# 05_LMS7002M_RF.net
KiCad netlist of a schematic drawn in Altium Designer
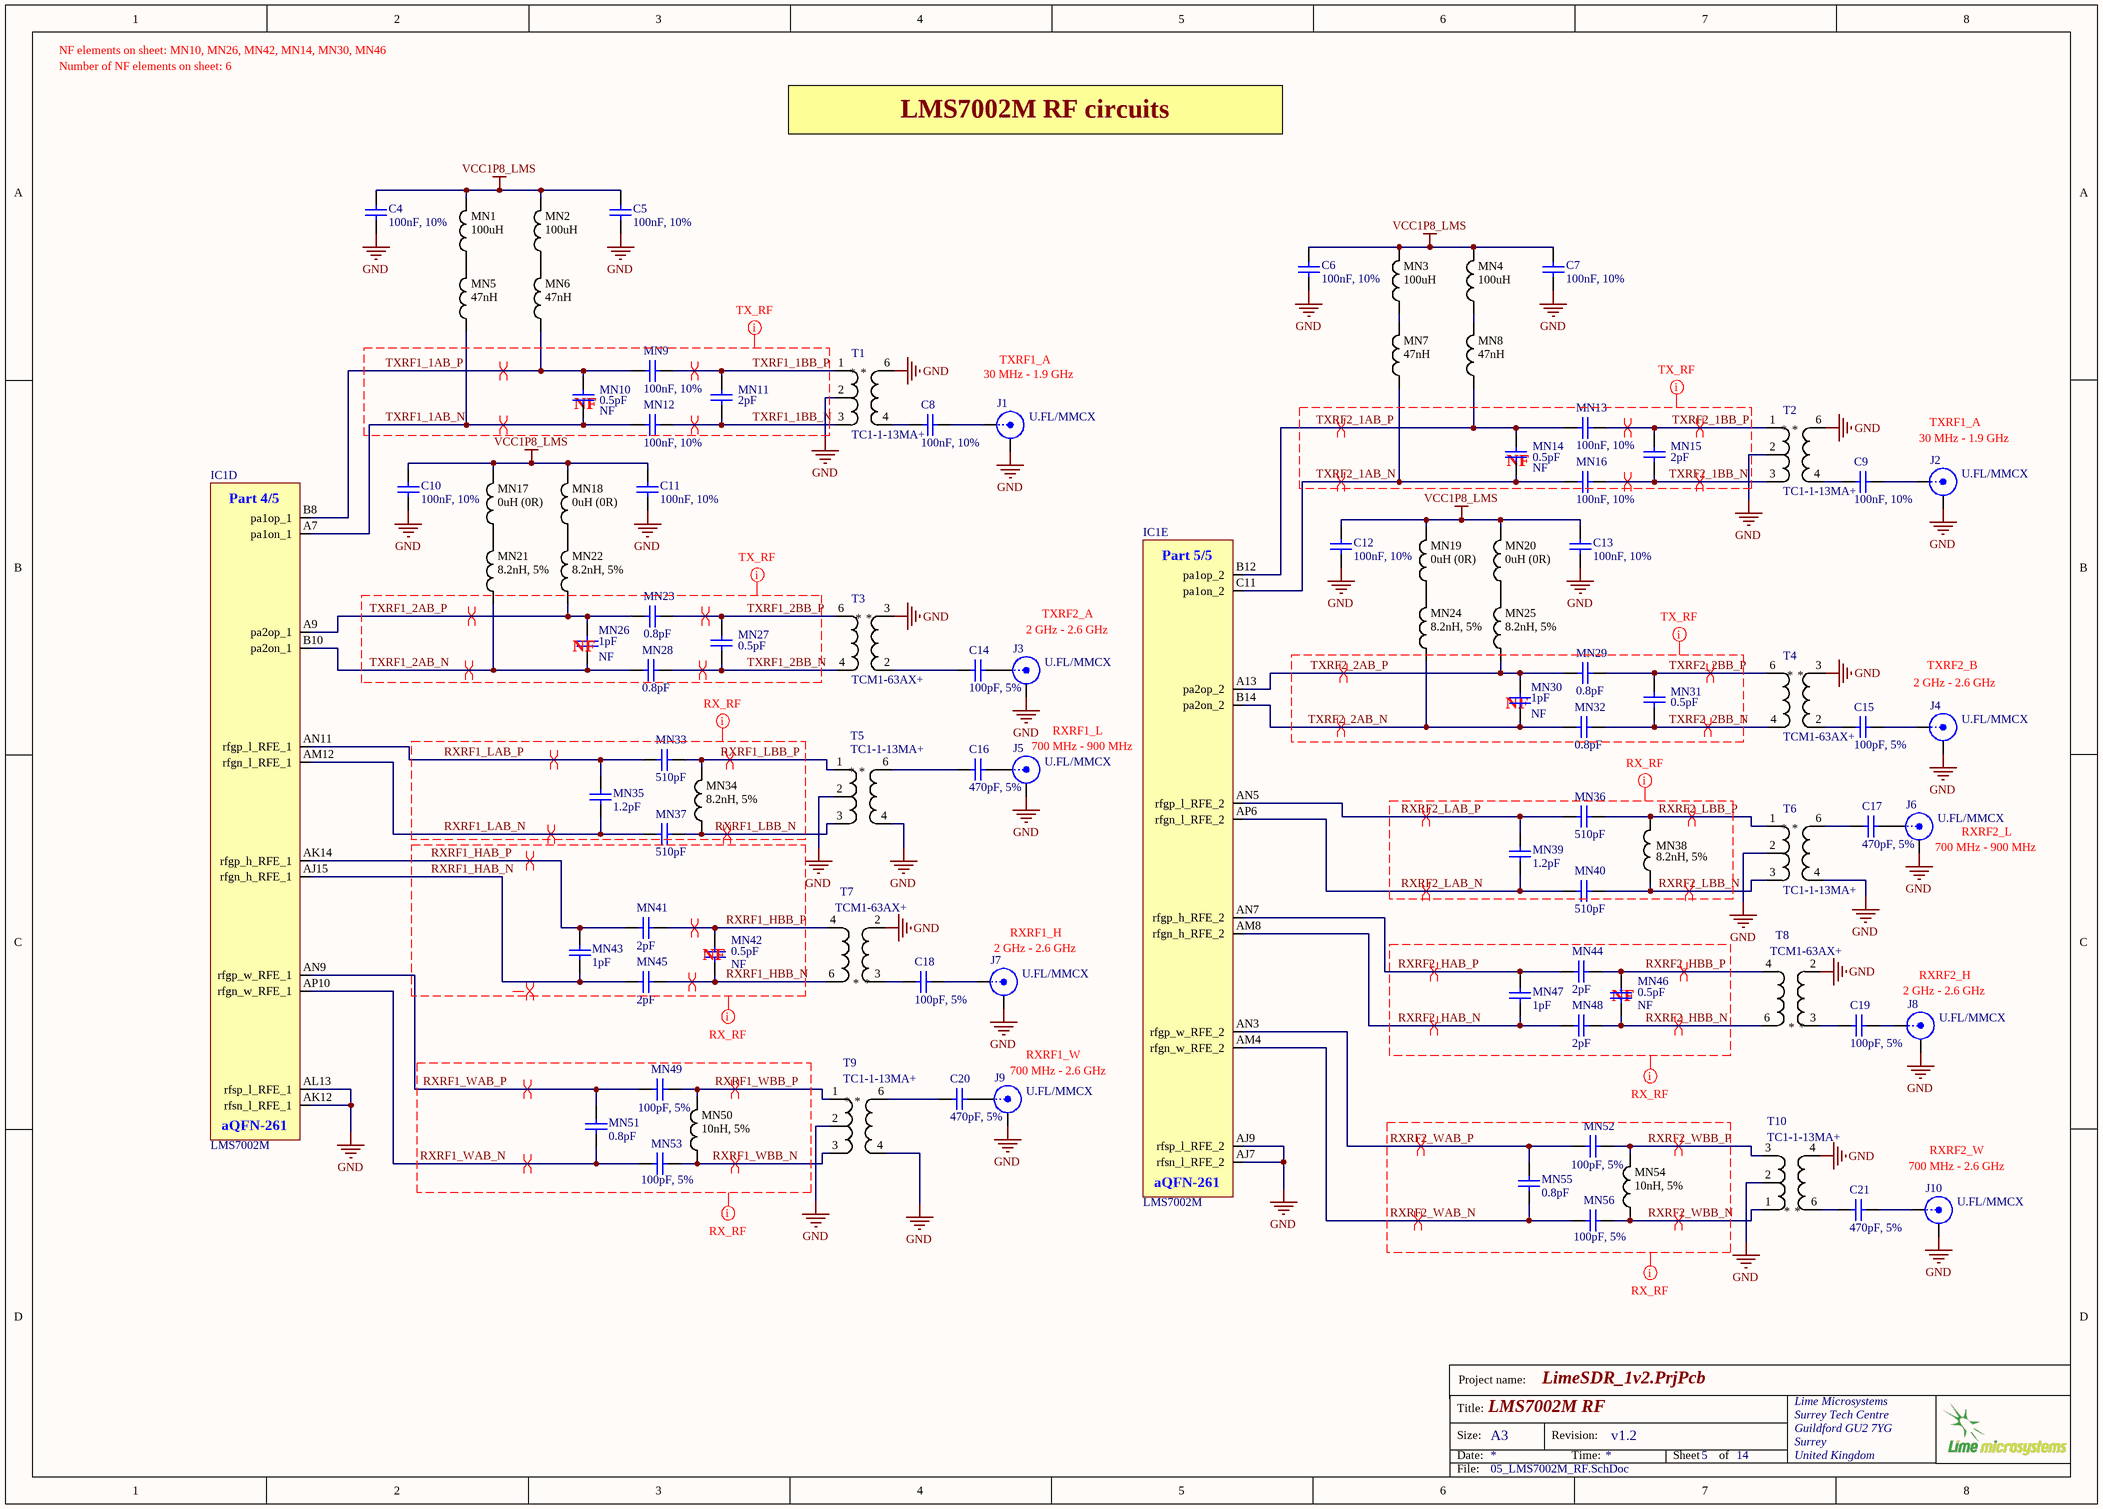
[diagram p0: 05_LMS7002M_RF.SchDoc]

(export (version "E")
  (design (tool "Eeschema 10.0.6"))
  (components
    (comp (ref "C4")
      (value "100nF, 10%")
      (footprint "CAP0402")
      (fields
        (field (name "MANUFACTURER") "Murata Electronics")
        (field (name "TOLERANCE") "10 %")
        (field (name "MANUFACTURER PART NUMBER") "GRM155R71C104KA88D")
      )
      (libsource (lib "LimeMicroAltiumLib_schLib") (part "Cap_0402"))
    )
    (comp (ref "C5")
      (value "100nF, 10%")
      (footprint "CAP0402")
      (fields
        (field (name "MANUFACTURER") "Murata Electronics")
        (field (name "TOLERANCE") "10 %")
        (field (name "MANUFACTURER PART NUMBER") "GRM155R71C104KA88D")
      )
      (libsource (lib "LimeMicroAltiumLib_schLib") (part "Cap_0402"))
    )
    (comp (ref "C6")
      (value "100nF, 10%")
      (footprint "CAP0402")
      (fields
        (field (name "MANUFACTURER") "Murata Electronics")
        (field (name "TOLERANCE") "10 %")
        (field (name "MANUFACTURER PART NUMBER") "GRM155R71C104KA88D")
      )
      (libsource (lib "LimeMicroAltiumLib_schLib") (part "Cap_0402"))
    )
    (comp (ref "C7")
      (value "100nF, 10%")
      (footprint "CAP0402")
      (fields
        (field (name "MANUFACTURER") "Murata Electronics")
        (field (name "TOLERANCE") "10 %")
        (field (name "MANUFACTURER PART NUMBER") "GRM155R71C104KA88D")
      )
      (libsource (lib "LimeMicroAltiumLib_schLib") (part "Cap_0402"))
    )
    (comp (ref "C8")
      (value "100nF, 10%")
      (footprint "CAP0402")
      (fields
        (field (name "MANUFACTURER") "Murata Electronics")
        (field (name "TOLERANCE") "10 %")
        (field (name "MANUFACTURER PART NUMBER") "GRM155R71C104KA88D")
      )
      (libsource (lib "LimeMicroAltiumLib_schLib") (part "Cap_0402"))
    )
    (comp (ref "C9")
      (value "100nF, 10%")
      (footprint "CAP0402")
      (fields
        (field (name "MANUFACTURER") "Murata Electronics")
        (field (name "TOLERANCE") "10 %")
        (field (name "MANUFACTURER PART NUMBER") "GRM155R71C104KA88D")
      )
      (libsource (lib "LimeMicroAltiumLib_schLib") (part "Cap_0402"))
    )
    (comp (ref "C10")
      (value "100nF, 10%")
      (footprint "CAP0402")
      (fields
        (field (name "MANUFACTURER") "Murata Electronics")
        (field (name "TOLERANCE") "10 %")
        (field (name "MANUFACTURER PART NUMBER") "GRM155R71C104KA88D")
      )
      (libsource (lib "LimeMicroAltiumLib_schLib") (part "Cap_0402"))
    )
    (comp (ref "C11")
      (value "100nF, 10%")
      (footprint "CAP0402")
      (fields
        (field (name "MANUFACTURER") "Murata Electronics")
        (field (name "TOLERANCE") "10 %")
        (field (name "MANUFACTURER PART NUMBER") "GRM155R71C104KA88D")
      )
      (libsource (lib "LimeMicroAltiumLib_schLib") (part "Cap_0402"))
    )
    (comp (ref "C12")
      (value "100nF, 10%")
      (footprint "CAP0402")
      (fields
        (field (name "MANUFACTURER") "Murata Electronics")
        (field (name "TOLERANCE") "10 %")
        (field (name "MANUFACTURER PART NUMBER") "GRM155R71C104KA88D")
      )
      (libsource (lib "LimeMicroAltiumLib_schLib") (part "Cap_0402"))
    )
    (comp (ref "C13")
      (value "100nF, 10%")
      (footprint "CAP0402")
      (fields
        (field (name "MANUFACTURER") "Murata Electronics")
        (field (name "TOLERANCE") "10 %")
        (field (name "MANUFACTURER PART NUMBER") "GRM155R71C104KA88D")
      )
      (libsource (lib "LimeMicroAltiumLib_schLib") (part "Cap_0402"))
    )
    (comp (ref "C14")
      (value "100pF, 5%")
      (footprint "CAP0402")
      (fields (field (name "TOLERANCE") "±5%") (field (name "MANUFACTURER") "Yageo"))
      (libsource (lib "LimeMicroAltiumLib_schLib") (part "Cap_0402"))
    )
    (comp (ref "C15")
      (value "100pF, 5%")
      (footprint "CAP0402")
      (fields (field (name "TOLERANCE") "±5%") (field (name "MANUFACTURER") "Yageo"))
      (libsource (lib "LimeMicroAltiumLib_schLib") (part "Cap_0402"))
    )
    (comp (ref "C16")
      (value "470pF, 5%")
      (footprint "CAP0402")
      (fields
        (field (name "MANUFACTURER PART NUMBER") "C1005C0G1H471J050BA")
        (field (name "TOLERANCE") "±5%")
        (field (name "MANUFACTURER") "TDK Corporation")
      )
      (libsource (lib "LimeMicroAltiumLib_schLib") (part "Cap_0402"))
    )
    (comp (ref "C17")
      (value "470pF, 5%")
      (footprint "CAP0402")
      (fields
        (field (name "MANUFACTURER PART NUMBER") "C1005C0G1H471J050BA")
        (field (name "TOLERANCE") "±5%")
        (field (name "MANUFACTURER") "TDK Corporation")
      )
      (libsource (lib "LimeMicroAltiumLib_schLib") (part "Cap_0402"))
    )
    (comp (ref "C18")
      (value "100pF, 5%")
      (footprint "CAP0402")
      (fields (field (name "TOLERANCE") "±5%") (field (name "MANUFACTURER") "Yageo"))
      (libsource (lib "LimeMicroAltiumLib_schLib") (part "Cap_0402"))
    )
    (comp (ref "C19")
      (value "100pF, 5%")
      (footprint "CAP0402")
      (fields (field (name "TOLERANCE") "±5%") (field (name "MANUFACTURER") "Yageo"))
      (libsource (lib "LimeMicroAltiumLib_schLib") (part "Cap_0402"))
    )
    (comp (ref "C20")
      (value "470pF, 5%")
      (footprint "CAP0402")
      (fields
        (field (name "MANUFACTURER PART NUMBER") "C1005C0G1H471J050BA")
        (field (name "TOLERANCE") "±5%")
        (field (name "MANUFACTURER") "TDK Corporation")
      )
      (libsource (lib "LimeMicroAltiumLib_schLib") (part "Cap_0402"))
    )
    (comp (ref "C21")
      (value "470pF, 5%")
      (footprint "CAP0402")
      (fields
        (field (name "MANUFACTURER PART NUMBER") "C1005C0G1H471J050BA")
        (field (name "TOLERANCE") "±5%")
        (field (name "MANUFACTURER") "TDK Corporation")
      )
      (libsource (lib "LimeMicroAltiumLib_schLib") (part "Cap_0402"))
    )
    (comp (ref "IC1")
      (value "LMS7002M")
      (footprint "LMS7002M")
      (fields (field (name "MANUFACTURER") "Lime Microsystems"))
      (libsource (lib "LimeMicroAltiumLib_schLib") (part "LMS7002M"))
    )
    (comp (ref "J1")
      (value "U.FL/MMCX")
      (footprint "MMCX_UFL_conn_u")
      (description "CONN UMC RCPT STR 50 OHM SMD")
      (fields (field (name "MANUFACTURER") "Molex, LLC"))
      (libsource (lib "LimeMicroAltiumLib_schLib") (part "RF_IF_connector"))
    )
    (comp (ref "J2")
      (value "U.FL/MMCX")
      (footprint "MMCX_UFL_conn_u")
      (description "CONN UMC RCPT STR 50 OHM SMD")
      (fields (field (name "MANUFACTURER") "Molex, LLC"))
      (libsource (lib "LimeMicroAltiumLib_schLib") (part "RF_IF_connector"))
    )
    (comp (ref "J3")
      (value "U.FL/MMCX")
      (footprint "MMCX_UFL_conn_u")
      (description "CONN UMC RCPT STR 50 OHM SMD")
      (fields (field (name "MANUFACTURER") "Molex, LLC"))
      (libsource (lib "LimeMicroAltiumLib_schLib") (part "RF_IF_connector"))
    )
    (comp (ref "J4")
      (value "U.FL/MMCX")
      (footprint "MMCX_UFL_conn_u")
      (description "CONN UMC RCPT STR 50 OHM SMD")
      (fields (field (name "MANUFACTURER") "Molex, LLC"))
      (libsource (lib "LimeMicroAltiumLib_schLib") (part "RF_IF_connector"))
    )
    (comp (ref "J5")
      (value "U.FL/MMCX")
      (footprint "MMCX_UFL_conn_u")
      (description "CONN UMC RCPT STR 50 OHM SMD")
      (fields (field (name "MANUFACTURER") "Molex, LLC"))
      (libsource (lib "LimeMicroAltiumLib_schLib") (part "RF_IF_connector"))
    )
    (comp (ref "J6")
      (value "U.FL/MMCX")
      (footprint "MMCX_UFL_conn_u")
      (description "CONN UMC RCPT STR 50 OHM SMD")
      (fields (field (name "MANUFACTURER") "Molex, LLC"))
      (libsource (lib "LimeMicroAltiumLib_schLib") (part "RF_IF_connector"))
    )
    (comp (ref "J7")
      (value "U.FL/MMCX")
      (footprint "MMCX_UFL_conn_u")
      (description "CONN UMC RCPT STR 50 OHM SMD")
      (fields (field (name "MANUFACTURER") "Molex, LLC"))
      (libsource (lib "LimeMicroAltiumLib_schLib") (part "RF_IF_connector"))
    )
    (comp (ref "J8")
      (value "U.FL/MMCX")
      (footprint "MMCX_UFL_conn_u")
      (description "CONN UMC RCPT STR 50 OHM SMD")
      (fields (field (name "MANUFACTURER") "Molex, LLC"))
      (libsource (lib "LimeMicroAltiumLib_schLib") (part "RF_IF_connector"))
    )
    (comp (ref "J9")
      (value "U.FL/MMCX")
      (footprint "MMCX_UFL_conn_u")
      (description "CONN UMC RCPT STR 50 OHM SMD")
      (fields (field (name "MANUFACTURER") "Molex, LLC"))
      (libsource (lib "LimeMicroAltiumLib_schLib") (part "RF_IF_connector"))
    )
    (comp (ref "J10")
      (value "U.FL/MMCX")
      (footprint "MMCX_UFL_conn_u")
      (description "CONN UMC RCPT STR 50 OHM SMD")
      (fields (field (name "MANUFACTURER") "Molex, LLC"))
      (libsource (lib "LimeMicroAltiumLib_schLib") (part "RF_IF_connector"))
    )
    (comp (ref "MN1")
      (value "100uH")
      (footprint "RES0805")
      (fields
        (field (name "TOLERANCE") "±10%")
        (field (name "MANUFACTURER") "TDK Corporation")
        (field (name "MANUFACTURER PART NUMBER") "MLF2012C101KT000")
      )
      (libsource (lib "LimeMicroAltiumLib_schLib") (part "Inductor_0603"))
    )
    (comp (ref "MN2")
      (value "100uH")
      (footprint "RES0805")
      (fields
        (field (name "TOLERANCE") "±10%")
        (field (name "MANUFACTURER") "TDK Corporation")
        (field (name "MANUFACTURER PART NUMBER") "MLF2012C101KT000")
      )
      (libsource (lib "LimeMicroAltiumLib_schLib") (part "Inductor_0603"))
    )
    (comp (ref "MN3")
      (value "100uH")
      (footprint "RES0805")
      (fields
        (field (name "TOLERANCE") "±10%")
        (field (name "MANUFACTURER") "TDK Corporation")
        (field (name "MANUFACTURER PART NUMBER") "MLF2012C101KT000")
      )
      (libsource (lib "LimeMicroAltiumLib_schLib") (part "Inductor_0603"))
    )
    (comp (ref "MN4")
      (value "100uH")
      (footprint "RES0805")
      (fields
        (field (name "TOLERANCE") "±10%")
        (field (name "MANUFACTURER") "TDK Corporation")
        (field (name "MANUFACTURER PART NUMBER") "MLF2012C101KT000")
      )
      (libsource (lib "LimeMicroAltiumLib_schLib") (part "Inductor_0603"))
    )
    (comp (ref "MN5")
      (value "47nH")
      (footprint "RES0402")
      (fields
        (field (name "MANUFACTURER") "COILCRAFT")
        (field (name "MANUFACTURER PART NUMBER") "0402HP-47NXJLU")
      )
      (libsource (lib "LimeMicroAltiumLib_schLib") (part "Inductor_0603"))
    )
    (comp (ref "MN6")
      (value "47nH")
      (footprint "RES0402")
      (fields
        (field (name "MANUFACTURER") "COILCRAFT")
        (field (name "MANUFACTURER PART NUMBER") "0402HP-47NXJLU")
      )
      (libsource (lib "LimeMicroAltiumLib_schLib") (part "Inductor_0603"))
    )
    (comp (ref "MN7")
      (value "47nH")
      (footprint "RES0402")
      (fields
        (field (name "MANUFACTURER") "COILCRAFT")
        (field (name "MANUFACTURER PART NUMBER") "0402HP-47NXJLU")
      )
      (libsource (lib "LimeMicroAltiumLib_schLib") (part "Inductor_0603"))
    )
    (comp (ref "MN8")
      (value "47nH")
      (footprint "RES0402")
      (fields
        (field (name "MANUFACTURER") "COILCRAFT")
        (field (name "MANUFACTURER PART NUMBER") "0402HP-47NXJLU")
      )
      (libsource (lib "LimeMicroAltiumLib_schLib") (part "Inductor_0603"))
    )
    (comp (ref "MN9")
      (value "100nF, 10%")
      (footprint "CAP0402")
      (fields
        (field (name "MANUFACTURER") "Murata Electronics")
        (field (name "TOLERANCE") "10 %")
        (field (name "MANUFACTURER PART NUMBER") "GRM155R71C104KA88D")
      )
      (libsource (lib "LimeMicroAltiumLib_schLib") (part "Cap_0402"))
    )
    (comp (ref "MN10")
      (value "0.5pF")
      (footprint "CAP0402")
      (fields
        (field (name "ASSEMBLY INFO") "NF")
        (field (name "TOLERANCE") "±0.25pF")
        (field (name "MANUFACTURER") "Yageo")
      )
      (libsource (lib "LimeMicroAltiumLib_schLib") (part "Cap_0402"))
    )
    (comp (ref "MN11")
      (value "2pF")
      (footprint "CAP0402")
      (fields (field (name "MANUFACTURER PART NUMBER") "04025U2R0BAT2A") (field (name "MANUFACTURER") "AVX"))
      (libsource (lib "LimeMicroAltiumLib_schLib") (part "Cap_0402"))
    )
    (comp (ref "MN12")
      (value "100nF, 10%")
      (footprint "CAP0402")
      (fields
        (field (name "MANUFACTURER") "Murata Electronics")
        (field (name "TOLERANCE") "10 %")
        (field (name "MANUFACTURER PART NUMBER") "GRM155R71C104KA88D")
      )
      (libsource (lib "LimeMicroAltiumLib_schLib") (part "Cap_0402"))
    )
    (comp (ref "MN13")
      (value "100nF, 10%")
      (footprint "CAP0402")
      (fields
        (field (name "MANUFACTURER") "Murata Electronics")
        (field (name "TOLERANCE") "10 %")
        (field (name "MANUFACTURER PART NUMBER") "GRM155R71C104KA88D")
      )
      (libsource (lib "LimeMicroAltiumLib_schLib") (part "Cap_0402"))
    )
    (comp (ref "MN14")
      (value "0.5pF")
      (footprint "CAP0402")
      (fields
        (field (name "ASSEMBLY INFO") "NF")
        (field (name "TOLERANCE") "±0.25pF")
        (field (name "MANUFACTURER") "Yageo")
      )
      (libsource (lib "LimeMicroAltiumLib_schLib") (part "Cap_0402"))
    )
    (comp (ref "MN15")
      (value "2pF")
      (footprint "CAP0402")
      (fields (field (name "MANUFACTURER PART NUMBER") "04025U2R0BAT2A") (field (name "MANUFACTURER") "AVX"))
      (libsource (lib "LimeMicroAltiumLib_schLib") (part "Cap_0402"))
    )
    (comp (ref "MN16")
      (value "100nF, 10%")
      (footprint "CAP0402")
      (fields
        (field (name "MANUFACTURER") "Murata Electronics")
        (field (name "TOLERANCE") "10 %")
        (field (name "MANUFACTURER PART NUMBER") "GRM155R71C104KA88D")
      )
      (libsource (lib "LimeMicroAltiumLib_schLib") (part "Cap_0402"))
    )
    (comp (ref "MN17")
      (value "0uH (0R)")
      (footprint "RES0805")
      (fields (field (name "MANUFACTURER") "BOURNS"))
      (libsource (lib "LimeMicroAltiumLib_schLib") (part "Inductor_0603"))
    )
    (comp (ref "MN18")
      (value "0uH (0R)")
      (footprint "RES0805")
      (fields (field (name "MANUFACTURER") "BOURNS"))
      (libsource (lib "LimeMicroAltiumLib_schLib") (part "Inductor_0603"))
    )
    (comp (ref "MN19")
      (value "0uH (0R)")
      (footprint "RES0805")
      (fields (field (name "MANUFACTURER") "BOURNS"))
      (libsource (lib "LimeMicroAltiumLib_schLib") (part "Inductor_0603"))
    )
    (comp (ref "MN20")
      (value "0uH (0R)")
      (footprint "RES0805")
      (fields (field (name "MANUFACTURER") "BOURNS"))
      (libsource (lib "LimeMicroAltiumLib_schLib") (part "Inductor_0603"))
    )
    (comp (ref "MN21")
      (value "8.2nH, 5%")
      (footprint "RES0402")
      (fields (field (name "MANUFACTURER") "COILCRAFT"))
      (libsource (lib "LimeMicroAltiumLib_schLib") (part "Inductor_0603"))
    )
    (comp (ref "MN22")
      (value "8.2nH, 5%")
      (footprint "RES0402")
      (fields (field (name "MANUFACTURER") "COILCRAFT"))
      (libsource (lib "LimeMicroAltiumLib_schLib") (part "Inductor_0603"))
    )
    (comp (ref "MN23")
      (value "0.8pF")
      (footprint "CAP0402")
      (fields
        (field (name "TOLERANCE") "±0.1pF")
        (field (name "MANUFACTURER") "Murata Electronics North America")
        (field (name "MANUFACTURER PART NUMBER") "GRM1555C1HR80BA01D")
      )
      (libsource (lib "LimeMicroAltiumLib_schLib") (part "Cap_0402"))
    )
    (comp (ref "MN24")
      (value "8.2nH, 5%")
      (footprint "RES0402")
      (fields (field (name "MANUFACTURER") "COILCRAFT"))
      (libsource (lib "LimeMicroAltiumLib_schLib") (part "Inductor_0603"))
    )
    (comp (ref "MN25")
      (value "8.2nH, 5%")
      (footprint "RES0402")
      (fields (field (name "MANUFACTURER") "COILCRAFT"))
      (libsource (lib "LimeMicroAltiumLib_schLib") (part "Inductor_0603"))
    )
    (comp (ref "MN26")
      (value "1pF")
      (footprint "CAP0402")
      (fields
        (field (name "ASSEMBLY INFO") "NF")
        (field (name "MANUFACTURER") "TDK Corporation")
        (field (name "TOLERANCE") "±0.1pF")
      )
      (libsource (lib "LimeMicroAltiumLib_schLib") (part "Cap_0402"))
    )
    (comp (ref "MN27")
      (value "0.5pF")
      (footprint "CAP0402")
      (fields (field (name "TOLERANCE") "±0.25pF") (field (name "MANUFACTURER") "Yageo"))
      (libsource (lib "LimeMicroAltiumLib_schLib") (part "Cap_0402"))
    )
    (comp (ref "MN28")
      (value "0.8pF")
      (footprint "CAP0402")
      (fields
        (field (name "TOLERANCE") "±0.1pF")
        (field (name "MANUFACTURER") "Murata Electronics North America")
        (field (name "MANUFACTURER PART NUMBER") "GRM1555C1HR80BA01D")
      )
      (libsource (lib "LimeMicroAltiumLib_schLib") (part "Cap_0402"))
    )
    (comp (ref "MN29")
      (value "0.8pF")
      (footprint "CAP0402")
      (fields
        (field (name "TOLERANCE") "±0.1pF")
        (field (name "MANUFACTURER") "Murata Electronics North America")
        (field (name "MANUFACTURER PART NUMBER") "GRM1555C1HR80BA01D")
      )
      (libsource (lib "LimeMicroAltiumLib_schLib") (part "Cap_0402"))
    )
    (comp (ref "MN30")
      (value "1pF")
      (footprint "CAP0402")
      (fields
        (field (name "ASSEMBLY INFO") "NF")
        (field (name "MANUFACTURER") "TDK Corporation")
        (field (name "TOLERANCE") "±0.1pF")
      )
      (libsource (lib "LimeMicroAltiumLib_schLib") (part "Cap_0402"))
    )
    (comp (ref "MN31")
      (value "0.5pF")
      (footprint "CAP0402")
      (fields (field (name "TOLERANCE") "±0.25pF") (field (name "MANUFACTURER") "Yageo"))
      (libsource (lib "LimeMicroAltiumLib_schLib") (part "Cap_0402"))
    )
    (comp (ref "MN32")
      (value "0.8pF")
      (footprint "CAP0402")
      (fields
        (field (name "TOLERANCE") "±0.1pF")
        (field (name "MANUFACTURER") "Murata Electronics North America")
        (field (name "MANUFACTURER PART NUMBER") "GRM1555C1HR80BA01D")
      )
      (libsource (lib "LimeMicroAltiumLib_schLib") (part "Cap_0402"))
    )
    (comp (ref "MN33")
      (value "510pF")
      (footprint "CAP0402")
      (fields
        (field (name "TOLERANCE") "±5%")
        (field (name "MANUFACTURER") "Murata Electronics North America")
        (field (name "MANUFACTURER PART NUMBER") "GRM1555C1H511JA01D")
      )
      (libsource (lib "LimeMicroAltiumLib_schLib") (part "Cap_0402"))
    )
    (comp (ref "MN34")
      (value "8.2nH, 5%")
      (footprint "RES0402")
      (fields (field (name "MANUFACTURER") "COILCRAFT"))
      (libsource (lib "LimeMicroAltiumLib_schLib") (part "Inductor_0603"))
    )
    (comp (ref "MN35")
      (value "1.2pF")
      (footprint "CAP0402")
      (fields
        (field (name "MANUFACTURER") "Murata Electronics North America")
        (field (name "MANUFACTURER PART NUMBER") "GRM1555C1H1R2CA01D")
        (field (name "TOLERANCE") "±0.25pF")
      )
      (libsource (lib "LimeMicroAltiumLib_schLib") (part "Cap_0402"))
    )
    (comp (ref "MN36")
      (value "510pF")
      (footprint "CAP0402")
      (fields
        (field (name "TOLERANCE") "±5%")
        (field (name "MANUFACTURER") "Murata Electronics North America")
        (field (name "MANUFACTURER PART NUMBER") "GRM1555C1H511JA01D")
      )
      (libsource (lib "LimeMicroAltiumLib_schLib") (part "Cap_0402"))
    )
    (comp (ref "MN37")
      (value "510pF")
      (footprint "CAP0402")
      (fields
        (field (name "TOLERANCE") "±5%")
        (field (name "MANUFACTURER") "Murata Electronics North America")
        (field (name "MANUFACTURER PART NUMBER") "GRM1555C1H511JA01D")
      )
      (libsource (lib "LimeMicroAltiumLib_schLib") (part "Cap_0402"))
    )
    (comp (ref "MN38")
      (value "8.2nH, 5%")
      (footprint "RES0402")
      (fields (field (name "MANUFACTURER") "COILCRAFT"))
      (libsource (lib "LimeMicroAltiumLib_schLib") (part "Inductor_0603"))
    )
    (comp (ref "MN39")
      (value "1.2pF")
      (footprint "CAP0402")
      (fields
        (field (name "MANUFACTURER") "Murata Electronics North America")
        (field (name "MANUFACTURER PART NUMBER") "GRM1555C1H1R2CA01D")
        (field (name "TOLERANCE") "±0.25pF")
      )
      (libsource (lib "LimeMicroAltiumLib_schLib") (part "Cap_0402"))
    )
    (comp (ref "MN40")
      (value "510pF")
      (footprint "CAP0402")
      (fields
        (field (name "TOLERANCE") "±5%")
        (field (name "MANUFACTURER") "Murata Electronics North America")
        (field (name "MANUFACTURER PART NUMBER") "GRM1555C1H511JA01D")
      )
      (libsource (lib "LimeMicroAltiumLib_schLib") (part "Cap_0402"))
    )
    (comp (ref "MN41")
      (value "2pF")
      (footprint "CAP0402")
      (fields (field (name "MANUFACTURER PART NUMBER") "04025U2R0BAT2A") (field (name "MANUFACTURER") "AVX"))
      (libsource (lib "LimeMicroAltiumLib_schLib") (part "Cap_0402"))
    )
    (comp (ref "MN42")
      (value "0.5pF")
      (footprint "CAP0402")
      (fields
        (field (name "ASSEMBLY INFO") "NF")
        (field (name "TOLERANCE") "±0.25pF")
        (field (name "MANUFACTURER") "Yageo")
      )
      (libsource (lib "LimeMicroAltiumLib_schLib") (part "Cap_0402"))
    )
    (comp (ref "MN43")
      (value "1pF")
      (footprint "CAP0402")
      (fields (field (name "MANUFACTURER") "TDK Corporation") (field (name "TOLERANCE") "±0.1pF"))
      (libsource (lib "LimeMicroAltiumLib_schLib") (part "Cap_0402"))
    )
    (comp (ref "MN44")
      (value "2pF")
      (footprint "CAP0402")
      (fields (field (name "MANUFACTURER PART NUMBER") "04025U2R0BAT2A") (field (name "MANUFACTURER") "AVX"))
      (libsource (lib "LimeMicroAltiumLib_schLib") (part "Cap_0402"))
    )
    (comp (ref "MN45")
      (value "2pF")
      (footprint "CAP0402")
      (fields (field (name "MANUFACTURER PART NUMBER") "04025U2R0BAT2A") (field (name "MANUFACTURER") "AVX"))
      (libsource (lib "LimeMicroAltiumLib_schLib") (part "Cap_0402"))
    )
    (comp (ref "MN46")
      (value "0.5pF")
      (footprint "CAP0402")
      (fields
        (field (name "ASSEMBLY INFO") "NF")
        (field (name "TOLERANCE") "±0.25pF")
        (field (name "MANUFACTURER") "Yageo")
      )
      (libsource (lib "LimeMicroAltiumLib_schLib") (part "Cap_0402"))
    )
    (comp (ref "MN47")
      (value "1pF")
      (footprint "CAP0402")
      (fields (field (name "MANUFACTURER") "TDK Corporation") (field (name "TOLERANCE") "±0.1pF"))
      (libsource (lib "LimeMicroAltiumLib_schLib") (part "Cap_0402"))
    )
    (comp (ref "MN48")
      (value "2pF")
      (footprint "CAP0402")
      (fields (field (name "MANUFACTURER PART NUMBER") "04025U2R0BAT2A") (field (name "MANUFACTURER") "AVX"))
      (libsource (lib "LimeMicroAltiumLib_schLib") (part "Cap_0402"))
    )
    (comp (ref "MN49")
      (value "100pF, 5%")
      (footprint "CAP0402")
      (fields (field (name "TOLERANCE") "±5%") (field (name "MANUFACTURER") "Yageo"))
      (libsource (lib "LimeMicroAltiumLib_schLib") (part "Cap_0402"))
    )
    (comp (ref "MN50")
      (value "10nH, 5%")
      (footprint "RES0402")
      (fields (field (name "MANUFACTURER") "COILCRAFT"))
      (libsource (lib "LimeMicroAltiumLib_schLib") (part "Inductor_0603"))
    )
    (comp (ref "MN51")
      (value "0.8pF")
      (footprint "CAP0402")
      (fields
        (field (name "TOLERANCE") "±0.1pF")
        (field (name "MANUFACTURER") "Murata Electronics North America")
        (field (name "MANUFACTURER PART NUMBER") "GRM1555C1HR80BA01D")
      )
      (libsource (lib "LimeMicroAltiumLib_schLib") (part "Cap_0402"))
    )
    (comp (ref "MN52")
      (value "100pF, 5%")
      (footprint "CAP0402")
      (fields (field (name "TOLERANCE") "±5%") (field (name "MANUFACTURER") "Yageo"))
      (libsource (lib "LimeMicroAltiumLib_schLib") (part "Cap_0402"))
    )
    (comp (ref "MN53")
      (value "100pF, 5%")
      (footprint "CAP0402")
      (fields (field (name "TOLERANCE") "±5%") (field (name "MANUFACTURER") "Yageo"))
      (libsource (lib "LimeMicroAltiumLib_schLib") (part "Cap_0402"))
    )
    (comp (ref "MN54")
      (value "10nH, 5%")
      (footprint "RES0402")
      (fields (field (name "MANUFACTURER") "COILCRAFT"))
      (libsource (lib "LimeMicroAltiumLib_schLib") (part "Inductor_0603"))
    )
    (comp (ref "MN55")
      (value "0.8pF")
      (footprint "CAP0402")
      (fields
        (field (name "TOLERANCE") "±0.1pF")
        (field (name "MANUFACTURER") "Murata Electronics North America")
        (field (name "MANUFACTURER PART NUMBER") "GRM1555C1HR80BA01D")
      )
      (libsource (lib "LimeMicroAltiumLib_schLib") (part "Cap_0402"))
    )
    (comp (ref "MN56")
      (value "100pF, 5%")
      (footprint "CAP0402")
      (fields (field (name "TOLERANCE") "±5%") (field (name "MANUFACTURER") "Yageo"))
      (libsource (lib "LimeMicroAltiumLib_schLib") (part "Cap_0402"))
    )
    (comp (ref "T1")
      (value "TC1-1-13MA+")
      (footprint "TC1-1-13MA+_v2")
      (fields (field (name "MANUFACTURER") "Mini-Circuits"))
      (libsource (lib "LimeMicroAltiumLib_schLib") (part "Balun"))
    )
    (comp (ref "T2")
      (value "TC1-1-13MA+")
      (footprint "TC1-1-13MA+_v2")
      (fields (field (name "MANUFACTURER") "Mini-Circuits"))
      (libsource (lib "LimeMicroAltiumLib_schLib") (part "Balun"))
    )
    (comp (ref "T3")
      (value "TCM1-63AX+")
      (footprint "TCM1-63AX+_v2")
      (fields (field (name "MANUFACTURER") "Mini-circuits"))
      (libsource (lib "LimeMicroAltiumLib_schLib") (part "Balun_v2"))
    )
    (comp (ref "T4")
      (value "TCM1-63AX+")
      (footprint "TCM1-63AX+_v2")
      (fields (field (name "MANUFACTURER") "Mini-circuits"))
      (libsource (lib "LimeMicroAltiumLib_schLib") (part "Balun_v2"))
    )
    (comp (ref "T5")
      (value "TC1-1-13MA+")
      (footprint "TC1-1-13MA+_v2")
      (fields (field (name "MANUFACTURER") "Mini-Circuits"))
      (libsource (lib "LimeMicroAltiumLib_schLib") (part "Balun"))
    )
    (comp (ref "T6")
      (value "TC1-1-13MA+")
      (footprint "TC1-1-13MA+_v2")
      (fields (field (name "MANUFACTURER") "Mini-Circuits"))
      (libsource (lib "LimeMicroAltiumLib_schLib") (part "Balun"))
    )
    (comp (ref "T7")
      (value "TCM1-63AX+")
      (footprint "TCM1-63AX+_v2")
      (fields (field (name "MANUFACTURER") "Mini-circuits"))
      (libsource (lib "") (part "Balun_v2_1"))
    )
    (comp (ref "T8")
      (value "TCM1-63AX+")
      (footprint "TCM1-63AX+_v2")
      (fields (field (name "MANUFACTURER") "Mini-circuits"))
      (libsource (lib "") (part "Balun_v2_1"))
    )
    (comp (ref "T9")
      (value "TC1-1-13MA+")
      (footprint "TC1-1-13MA+_v2")
      (fields (field (name "MANUFACTURER") "Mini-Circuits"))
      (libsource (lib "LimeMicroAltiumLib_schLib") (part "Balun"))
    )
    (comp (ref "T10")
      (value "TC1-1-13MA+")
      (footprint "TC1-1-13MA+_v2")
      (fields (field (name "MANUFACTURER") "Mini-Circuits"))
      (libsource (lib "") (part "Balun_1"))
    )
  )
  (nets
    (net (code "1") (name "/RXRF1_HAB_N") (class "Default")
      (node (ref "IC1") (pin "AJ15") (pinfunction "rfgn_h_RFE_1_AJ15") (pintype "passive"))
      (node (ref "MN43") (pin "1") (pinfunction "1_1") (pintype "passive"))
      (node (ref "MN45") (pin "2") (pinfunction "2_2") (pintype "passive"))
    )
    (net (code "2") (name "/RXRF1_HAB_P") (class "Default")
      (node (ref "IC1") (pin "AK14") (pinfunction "rfgp_h_RFE_1_AK14") (pintype "passive"))
      (node (ref "MN41") (pin "2") (pinfunction "2_2") (pintype "passive"))
      (node (ref "MN43") (pin "2") (pinfunction "2_2") (pintype "passive"))
    )
    (net (code "3") (name "/RXRF1_HBB_N") (class "Default")
      (node (ref "MN42") (pin "1") (pinfunction "1_1") (pintype "passive"))
      (node (ref "MN45") (pin "1") (pinfunction "1_1") (pintype "passive"))
      (node (ref "T7") (pin "6") (pinfunction "6_6") (pintype "passive"))
    )
    (net (code "4") (name "/RXRF1_HBB_P") (class "Default")
      (node (ref "MN41") (pin "1") (pinfunction "1_1") (pintype "passive"))
      (node (ref "MN42") (pin "2") (pinfunction "2_2") (pintype "passive"))
      (node (ref "T7") (pin "4") (pinfunction "4_4") (pintype "passive"))
    )
    (net (code "5") (name "/RXRF1_LAB_N") (class "Default")
      (node (ref "IC1") (pin "AM12") (pinfunction "rfgn_l_RFE_1_AM12") (pintype "passive"))
      (node (ref "MN35") (pin "1") (pinfunction "1_1") (pintype "passive"))
      (node (ref "MN37") (pin "2") (pinfunction "2_2") (pintype "passive"))
    )
    (net (code "6") (name "/RXRF1_LAB_P") (class "Default")
      (node (ref "IC1") (pin "AN11") (pinfunction "rfgp_l_RFE_1_AN11") (pintype "passive"))
      (node (ref "MN33") (pin "2") (pinfunction "2_2") (pintype "passive"))
      (node (ref "MN35") (pin "2") (pinfunction "2_2") (pintype "passive"))
    )
    (net (code "7") (name "/RXRF1_LBB_N") (class "Default")
      (node (ref "MN34") (pin "1") (pinfunction "1_1") (pintype "passive"))
      (node (ref "MN37") (pin "1") (pinfunction "1_1") (pintype "passive"))
      (node (ref "T5") (pin "3") (pinfunction "3_3") (pintype "passive"))
    )
    (net (code "8") (name "/RXRF1_LBB_P") (class "Default")
      (node (ref "MN33") (pin "1") (pinfunction "1_1") (pintype "passive"))
      (node (ref "MN34") (pin "2") (pinfunction "2_2") (pintype "passive"))
      (node (ref "T5") (pin "1") (pinfunction "1_1") (pintype "passive"))
    )
    (net (code "9") (name "/RXRF1_WAB_N") (class "Default")
      (node (ref "IC1") (pin "AP10") (pinfunction "rfgn_w_RFE_1_AP10") (pintype "passive"))
      (node (ref "MN51") (pin "2") (pinfunction "2_2") (pintype "passive"))
      (node (ref "MN53") (pin "2") (pinfunction "2_2") (pintype "passive"))
    )
    (net (code "10") (name "/RXRF1_WAB_P") (class "Default")
      (node (ref "IC1") (pin "AN9") (pinfunction "rfgp_w_RFE_1_AN9") (pintype "passive"))
      (node (ref "MN49") (pin "2") (pinfunction "2_2") (pintype "passive"))
      (node (ref "MN51") (pin "1") (pinfunction "1_1") (pintype "passive"))
    )
    (net (code "11") (name "/RXRF1_WBB_N") (class "Default")
      (node (ref "MN50") (pin "1") (pinfunction "1_1") (pintype "passive"))
      (node (ref "MN53") (pin "1") (pinfunction "1_1") (pintype "passive"))
      (node (ref "T9") (pin "3") (pinfunction "3_3") (pintype "passive"))
    )
    (net (code "12") (name "/RXRF1_WBB_P") (class "Default")
      (node (ref "MN49") (pin "1") (pinfunction "1_1") (pintype "passive"))
      (node (ref "MN50") (pin "2") (pinfunction "2_2") (pintype "passive"))
      (node (ref "T9") (pin "1") (pinfunction "1_1") (pintype "passive"))
    )
    (net (code "13") (name "/RXRF2_HAB_N") (class "Default")
      (node (ref "IC1") (pin "AM8") (pinfunction "rfgn_h_RFE_2_AM8") (pintype "passive"))
      (node (ref "MN47") (pin "1") (pinfunction "1_1") (pintype "passive"))
      (node (ref "MN48") (pin "2") (pinfunction "2_2") (pintype "passive"))
    )
    (net (code "14") (name "/RXRF2_HAB_P") (class "Default")
      (node (ref "IC1") (pin "AN7") (pinfunction "rfgp_h_RFE_2_AN7") (pintype "passive"))
      (node (ref "MN44") (pin "2") (pinfunction "2_2") (pintype "passive"))
      (node (ref "MN47") (pin "2") (pinfunction "2_2") (pintype "passive"))
    )
    (net (code "15") (name "/RXRF2_HBB_N") (class "Default")
      (node (ref "MN46") (pin "1") (pinfunction "1_1") (pintype "passive"))
      (node (ref "MN48") (pin "1") (pinfunction "1_1") (pintype "passive"))
      (node (ref "T8") (pin "6") (pinfunction "6_6") (pintype "passive"))
    )
    (net (code "16") (name "/RXRF2_HBB_P") (class "Default")
      (node (ref "MN44") (pin "1") (pinfunction "1_1") (pintype "passive"))
      (node (ref "MN46") (pin "2") (pinfunction "2_2") (pintype "passive"))
      (node (ref "T8") (pin "4") (pinfunction "4_4") (pintype "passive"))
    )
    (net (code "17") (name "/RXRF2_LAB_N") (class "Default")
      (node (ref "IC1") (pin "AP6") (pinfunction "rfgn_l_RFE_2_AP6") (pintype "passive"))
      (node (ref "MN39") (pin "1") (pinfunction "1_1") (pintype "passive"))
      (node (ref "MN40") (pin "2") (pinfunction "2_2") (pintype "passive"))
    )
    (net (code "18") (name "/RXRF2_LAB_P") (class "Default")
      (node (ref "IC1") (pin "AN5") (pinfunction "rfgp_l_RFE_2_AN5") (pintype "passive"))
      (node (ref "MN36") (pin "2") (pinfunction "2_2") (pintype "passive"))
      (node (ref "MN39") (pin "2") (pinfunction "2_2") (pintype "passive"))
    )
    (net (code "19") (name "/RXRF2_LBB_N") (class "Default")
      (node (ref "MN38") (pin "1") (pinfunction "1_1") (pintype "passive"))
      (node (ref "MN40") (pin "1") (pinfunction "1_1") (pintype "passive"))
      (node (ref "T6") (pin "3") (pinfunction "3_3") (pintype "passive"))
    )
    (net (code "20") (name "/RXRF2_LBB_P") (class "Default")
      (node (ref "MN36") (pin "1") (pinfunction "1_1") (pintype "passive"))
      (node (ref "MN38") (pin "2") (pinfunction "2_2") (pintype "passive"))
      (node (ref "T6") (pin "1") (pinfunction "1_1") (pintype "passive"))
    )
    (net (code "21") (name "/RXRF2_WAB_N") (class "Default")
      (node (ref "IC1") (pin "AM4") (pinfunction "rfgn_w_RFE_2_AM4") (pintype "passive"))
      (node (ref "MN55") (pin "2") (pinfunction "2_2") (pintype "passive"))
      (node (ref "MN56") (pin "2") (pinfunction "2_2") (pintype "passive"))
    )
    (net (code "22") (name "/RXRF2_WAB_P") (class "Default")
      (node (ref "IC1") (pin "AN3") (pinfunction "rfgp_w_RFE_2_AN3") (pintype "passive"))
      (node (ref "MN52") (pin "2") (pinfunction "2_2") (pintype "passive"))
      (node (ref "MN55") (pin "1") (pinfunction "1_1") (pintype "passive"))
    )
    (net (code "23") (name "/RXRF2_WBB_N") (class "Default")
      (node (ref "MN54") (pin "1") (pinfunction "1_1") (pintype "passive"))
      (node (ref "MN56") (pin "1") (pinfunction "1_1") (pintype "passive"))
      (node (ref "T10") (pin "1") (pinfunction "1_1") (pintype "passive"))
    )
    (net (code "24") (name "/RXRF2_WBB_P") (class "Default")
      (node (ref "MN52") (pin "1") (pinfunction "1_1") (pintype "passive"))
      (node (ref "MN54") (pin "2") (pinfunction "2_2") (pintype "passive"))
      (node (ref "T10") (pin "3") (pinfunction "3_3") (pintype "passive"))
    )
    (net (code "25") (name "/TXRF1_1AB_N") (class "Default")
      (node (ref "IC1") (pin "A7") (pinfunction "pa1on_1_A7") (pintype "passive"))
      (node (ref "MN10") (pin "1") (pinfunction "1_1") (pintype "passive"))
      (node (ref "MN12") (pin "1") (pinfunction "1_1") (pintype "passive"))
      (node (ref "MN5") (pin "1") (pinfunction "1_1") (pintype "passive"))
    )
    (net (code "26") (name "/TXRF1_1AB_P") (class "Default")
      (node (ref "IC1") (pin "B8") (pinfunction "pa1op_1_B8") (pintype "passive"))
      (node (ref "MN10") (pin "2") (pinfunction "2_2") (pintype "passive"))
      (node (ref "MN6") (pin "1") (pinfunction "1_1") (pintype "passive"))
      (node (ref "MN9") (pin "2") (pinfunction "2_2") (pintype "passive"))
    )
    (net (code "27") (name "/TXRF1_1BB_N") (class "Default")
      (node (ref "MN11") (pin "1") (pinfunction "1_1") (pintype "passive"))
      (node (ref "MN12") (pin "2") (pinfunction "2_2") (pintype "passive"))
      (node (ref "T1") (pin "3") (pinfunction "3_3") (pintype "passive"))
    )
    (net (code "28") (name "/TXRF1_1BB_P") (class "Default")
      (node (ref "MN11") (pin "2") (pinfunction "2_2") (pintype "passive"))
      (node (ref "MN9") (pin "1") (pinfunction "1_1") (pintype "passive"))
      (node (ref "T1") (pin "1") (pinfunction "1_1") (pintype "passive"))
    )
    (net (code "29") (name "/TXRF1_2AB_N") (class "Default")
      (node (ref "IC1") (pin "B10") (pinfunction "pa2on_1_B10") (pintype "passive"))
      (node (ref "MN21") (pin "1") (pinfunction "1_1") (pintype "passive"))
      (node (ref "MN26") (pin "2") (pinfunction "2_2") (pintype "passive"))
      (node (ref "MN28") (pin "2") (pinfunction "2_2") (pintype "passive"))
    )
    (net (code "30") (name "/TXRF1_2AB_P") (class "Default")
      (node (ref "IC1") (pin "A9") (pinfunction "pa2op_1_A9") (pintype "passive"))
      (node (ref "MN22") (pin "1") (pinfunction "1_1") (pintype "passive"))
      (node (ref "MN23") (pin "2") (pinfunction "2_2") (pintype "passive"))
      (node (ref "MN26") (pin "1") (pinfunction "1_1") (pintype "passive"))
    )
    (net (code "31") (name "/TXRF1_2BB_N") (class "Default")
      (node (ref "MN27") (pin "1") (pinfunction "1_1") (pintype "passive"))
      (node (ref "MN28") (pin "1") (pinfunction "1_1") (pintype "passive"))
      (node (ref "T3") (pin "4") (pinfunction "4_4") (pintype "passive"))
    )
    (net (code "32") (name "/TXRF1_2BB_P") (class "Default")
      (node (ref "MN23") (pin "1") (pinfunction "1_1") (pintype "passive"))
      (node (ref "MN27") (pin "2") (pinfunction "2_2") (pintype "passive"))
      (node (ref "T3") (pin "6") (pinfunction "6_6") (pintype "passive"))
    )
    (net (code "33") (name "/TXRF2_1AB_N") (class "Default")
      (node (ref "IC1") (pin "C11") (pinfunction "pa1on_2_C11") (pintype "passive"))
      (node (ref "MN14") (pin "1") (pinfunction "1_1") (pintype "passive"))
      (node (ref "MN16") (pin "1") (pinfunction "1_1") (pintype "passive"))
      (node (ref "MN7") (pin "1") (pinfunction "1_1") (pintype "passive"))
    )
    (net (code "34") (name "/TXRF2_1AB_P") (class "Default")
      (node (ref "IC1") (pin "B12") (pinfunction "pa1op_2_B12") (pintype "passive"))
      (node (ref "MN13") (pin "2") (pinfunction "2_2") (pintype "passive"))
      (node (ref "MN14") (pin "2") (pinfunction "2_2") (pintype "passive"))
      (node (ref "MN8") (pin "1") (pinfunction "1_1") (pintype "passive"))
    )
    (net (code "35") (name "/TXRF2_1BB_N") (class "Default")
      (node (ref "MN15") (pin "1") (pinfunction "1_1") (pintype "passive"))
      (node (ref "MN16") (pin "2") (pinfunction "2_2") (pintype "passive"))
      (node (ref "T2") (pin "3") (pinfunction "3_3") (pintype "passive"))
    )
    (net (code "36") (name "/TXRF2_1BB_P") (class "Default")
      (node (ref "MN13") (pin "1") (pinfunction "1_1") (pintype "passive"))
      (node (ref "MN15") (pin "2") (pinfunction "2_2") (pintype "passive"))
      (node (ref "T2") (pin "1") (pinfunction "1_1") (pintype "passive"))
    )
    (net (code "37") (name "/TXRF2_2AB_N") (class "Default")
      (node (ref "IC1") (pin "B14") (pinfunction "pa2on_2_B14") (pintype "passive"))
      (node (ref "MN24") (pin "1") (pinfunction "1_1") (pintype "passive"))
      (node (ref "MN30") (pin "2") (pinfunction "2_2") (pintype "passive"))
      (node (ref "MN32") (pin "2") (pinfunction "2_2") (pintype "passive"))
    )
    (net (code "38") (name "/TXRF2_2AB_P") (class "Default")
      (node (ref "IC1") (pin "A13") (pinfunction "pa2op_2_A13") (pintype "passive"))
      (node (ref "MN25") (pin "1") (pinfunction "1_1") (pintype "passive"))
      (node (ref "MN29") (pin "2") (pinfunction "2_2") (pintype "passive"))
      (node (ref "MN30") (pin "1") (pinfunction "1_1") (pintype "passive"))
    )
    (net (code "39") (name "/TXRF2_2BB_N") (class "Default")
      (node (ref "MN31") (pin "1") (pinfunction "1_1") (pintype "passive"))
      (node (ref "MN32") (pin "1") (pinfunction "1_1") (pintype "passive"))
      (node (ref "T4") (pin "4") (pinfunction "4_4") (pintype "passive"))
    )
    (net (code "40") (name "/TXRF2_2BB_P") (class "Default")
      (node (ref "MN29") (pin "1") (pinfunction "1_1") (pintype "passive"))
      (node (ref "MN31") (pin "2") (pinfunction "2_2") (pintype "passive"))
      (node (ref "T4") (pin "6") (pinfunction "6_6") (pintype "passive"))
    )
    (net (code "41") (name "GND") (class "Default")
      (node (ref "C10") (pin "1") (pinfunction "1_1") (pintype "passive"))
      (node (ref "C11") (pin "1") (pinfunction "1_1") (pintype "passive"))
      (node (ref "C12") (pin "1") (pinfunction "1_1") (pintype "passive"))
      (node (ref "C13") (pin "1") (pinfunction "1_1") (pintype "passive"))
      (node (ref "C4") (pin "1") (pinfunction "1_1") (pintype "passive"))
      (node (ref "C5") (pin "1") (pinfunction "1_1") (pintype "passive"))
      (node (ref "C6") (pin "1") (pinfunction "1_1") (pintype "passive"))
      (node (ref "C7") (pin "1") (pinfunction "1_1") (pintype "passive"))
      (node (ref "IC1") (pin "AJ7") (pinfunction "rfsn_l_RFE_2_AJ7") (pintype "passive"))
      (node (ref "IC1") (pin "AJ9") (pinfunction "rfsp_l_RFE_2_AJ9") (pintype "passive"))
      (node (ref "IC1") (pin "AK12") (pinfunction "rfsn_l_RFE_1_AK12") (pintype "passive"))
      (node (ref "IC1") (pin "AL13") (pinfunction "rfsp_l_RFE_1_AL13") (pintype "passive"))
      (node (ref "J1") (pin "2") (pinfunction "Y_2") (pintype "passive"))
      (node (ref "J10") (pin "2") (pinfunction "Y_2") (pintype "passive"))
      (node (ref "J2") (pin "2") (pinfunction "Y_2") (pintype "passive"))
      (node (ref "J3") (pin "2") (pinfunction "Y_2") (pintype "passive"))
      (node (ref "J4") (pin "2") (pinfunction "Y_2") (pintype "passive"))
      (node (ref "J5") (pin "2") (pinfunction "Y_2") (pintype "passive"))
      (node (ref "J6") (pin "2") (pinfunction "Y_2") (pintype "passive"))
      (node (ref "J7") (pin "2") (pinfunction "Y_2") (pintype "passive"))
      (node (ref "J8") (pin "2") (pinfunction "Y_2") (pintype "passive"))
      (node (ref "J9") (pin "2") (pinfunction "Y_2") (pintype "passive"))
      (node (ref "T1") (pin "2") (pinfunction "2_2") (pintype "passive"))
      (node (ref "T1") (pin "6") (pinfunction "6_6") (pintype "passive"))
      (node (ref "T10") (pin "2") (pinfunction "2_2") (pintype "passive"))
      (node (ref "T10") (pin "4") (pinfunction "4_4") (pintype "passive"))
      (node (ref "T2") (pin "2") (pinfunction "2_2") (pintype "passive"))
      (node (ref "T2") (pin "6") (pinfunction "6_6") (pintype "passive"))
      (node (ref "T3") (pin "3") (pinfunction "3_3") (pintype "passive"))
      (node (ref "T4") (pin "3") (pinfunction "3_3") (pintype "passive"))
      (node (ref "T5") (pin "2") (pinfunction "2_2") (pintype "passive"))
      (node (ref "T5") (pin "4") (pinfunction "4_4") (pintype "passive"))
      (node (ref "T6") (pin "2") (pinfunction "2_2") (pintype "passive"))
      (node (ref "T6") (pin "4") (pinfunction "4_4") (pintype "passive"))
      (node (ref "T7") (pin "2") (pinfunction "2_2") (pintype "passive"))
      (node (ref "T8") (pin "2") (pinfunction "2_2") (pintype "passive"))
      (node (ref "T9") (pin "2") (pinfunction "2_2") (pintype "passive"))
      (node (ref "T9") (pin "4") (pinfunction "4_4") (pintype "passive"))
    )
    (net (code "42") (name "Net-(C8-Pad2)") (class "Default")
      (node (ref "C8") (pin "2") (pinfunction "2_2") (pintype "passive"))
      (node (ref "T1") (pin "4") (pinfunction "4_4") (pintype "passive"))
    )
    (net (code "43") (name "Net-(C9-Pad2)") (class "Default")
      (node (ref "C9") (pin "2") (pinfunction "2_2") (pintype "passive"))
      (node (ref "T2") (pin "4") (pinfunction "4_4") (pintype "passive"))
    )
    (net (code "44") (name "Net-(C14-Pad2)") (class "Default")
      (node (ref "C14") (pin "2") (pinfunction "2_2") (pintype "passive"))
      (node (ref "T3") (pin "2") (pinfunction "2_2") (pintype "passive"))
    )
    (net (code "45") (name "Net-(C15-Pad2)") (class "Default")
      (node (ref "C15") (pin "2") (pinfunction "2_2") (pintype "passive"))
      (node (ref "T4") (pin "2") (pinfunction "2_2") (pintype "passive"))
    )
    (net (code "46") (name "Net-(C16-Pad2)") (class "Default")
      (node (ref "C16") (pin "2") (pinfunction "2_2") (pintype "passive"))
      (node (ref "T5") (pin "6") (pinfunction "6_6") (pintype "passive"))
    )
    (net (code "47") (name "Net-(C17-Pad2)") (class "Default")
      (node (ref "C17") (pin "2") (pinfunction "2_2") (pintype "passive"))
      (node (ref "T6") (pin "6") (pinfunction "6_6") (pintype "passive"))
    )
    (net (code "48") (name "Net-(C18-Pad2)") (class "Default")
      (node (ref "C18") (pin "2") (pinfunction "2_2") (pintype "passive"))
      (node (ref "T7") (pin "3") (pinfunction "3_3") (pintype "passive"))
    )
    (net (code "49") (name "Net-(C19-Pad2)") (class "Default")
      (node (ref "C19") (pin "2") (pinfunction "2_2") (pintype "passive"))
      (node (ref "T8") (pin "3") (pinfunction "3_3") (pintype "passive"))
    )
    (net (code "50") (name "Net-(C20-Pad2)") (class "Default")
      (node (ref "C20") (pin "2") (pinfunction "2_2") (pintype "passive"))
      (node (ref "T9") (pin "6") (pinfunction "6_6") (pintype "passive"))
    )
    (net (code "51") (name "Net-(C21-Pad2)") (class "Default")
      (node (ref "C21") (pin "2") (pinfunction "2_2") (pintype "passive"))
      (node (ref "T10") (pin "6") (pinfunction "6_6") (pintype "passive"))
    )
    (net (code "52") (name "Net-(J1-X)") (class "Default")
      (node (ref "C8") (pin "1") (pinfunction "1_1") (pintype "passive"))
      (node (ref "J1") (pin "1") (pinfunction "X_1") (pintype "passive"))
    )
    (net (code "53") (name "Net-(J2-X)") (class "Default")
      (node (ref "C9") (pin "1") (pinfunction "1_1") (pintype "passive"))
      (node (ref "J2") (pin "1") (pinfunction "X_1") (pintype "passive"))
    )
    (net (code "54") (name "Net-(J3-X)") (class "Default")
      (node (ref "C14") (pin "1") (pinfunction "1_1") (pintype "passive"))
      (node (ref "J3") (pin "1") (pinfunction "X_1") (pintype "passive"))
    )
    (net (code "55") (name "Net-(J4-X)") (class "Default")
      (node (ref "C15") (pin "1") (pinfunction "1_1") (pintype "passive"))
      (node (ref "J4") (pin "1") (pinfunction "X_1") (pintype "passive"))
    )
    (net (code "56") (name "Net-(J5-X)") (class "Default")
      (node (ref "C16") (pin "1") (pinfunction "1_1") (pintype "passive"))
      (node (ref "J5") (pin "1") (pinfunction "X_1") (pintype "passive"))
    )
    (net (code "57") (name "Net-(J6-X)") (class "Default")
      (node (ref "C17") (pin "1") (pinfunction "1_1") (pintype "passive"))
      (node (ref "J6") (pin "1") (pinfunction "X_1") (pintype "passive"))
    )
    (net (code "58") (name "Net-(J7-X)") (class "Default")
      (node (ref "C18") (pin "1") (pinfunction "1_1") (pintype "passive"))
      (node (ref "J7") (pin "1") (pinfunction "X_1") (pintype "passive"))
    )
    (net (code "59") (name "Net-(J8-X)") (class "Default")
      (node (ref "C19") (pin "1") (pinfunction "1_1") (pintype "passive"))
      (node (ref "J8") (pin "1") (pinfunction "X_1") (pintype "passive"))
    )
    (net (code "60") (name "Net-(J9-X)") (class "Default")
      (node (ref "C20") (pin "1") (pinfunction "1_1") (pintype "passive"))
      (node (ref "J9") (pin "1") (pinfunction "X_1") (pintype "passive"))
    )
    (net (code "61") (name "Net-(J10-X)") (class "Default")
      (node (ref "C21") (pin "1") (pinfunction "1_1") (pintype "passive"))
      (node (ref "J10") (pin "1") (pinfunction "X_1") (pintype "passive"))
    )
    (net (code "62") (name "Net-(MN1-Pad1)") (class "Default")
      (node (ref "MN1") (pin "1") (pinfunction "1_1") (pintype "passive"))
      (node (ref "MN5") (pin "2") (pinfunction "2_2") (pintype "passive"))
    )
    (net (code "63") (name "Net-(MN2-Pad1)") (class "Default")
      (node (ref "MN2") (pin "1") (pinfunction "1_1") (pintype "passive"))
      (node (ref "MN6") (pin "2") (pinfunction "2_2") (pintype "passive"))
    )
    (net (code "64") (name "Net-(MN3-Pad1)") (class "Default")
      (node (ref "MN3") (pin "1") (pinfunction "1_1") (pintype "passive"))
      (node (ref "MN7") (pin "2") (pinfunction "2_2") (pintype "passive"))
    )
    (net (code "65") (name "Net-(MN4-Pad1)") (class "Default")
      (node (ref "MN4") (pin "1") (pinfunction "1_1") (pintype "passive"))
      (node (ref "MN8") (pin "2") (pinfunction "2_2") (pintype "passive"))
    )
    (net (code "66") (name "Net-(MN17-Pad1)") (class "Default")
      (node (ref "MN17") (pin "1") (pinfunction "1_1") (pintype "passive"))
      (node (ref "MN21") (pin "2") (pinfunction "2_2") (pintype "passive"))
    )
    (net (code "67") (name "Net-(MN18-Pad1)") (class "Default")
      (node (ref "MN18") (pin "1") (pinfunction "1_1") (pintype "passive"))
      (node (ref "MN22") (pin "2") (pinfunction "2_2") (pintype "passive"))
    )
    (net (code "68") (name "Net-(MN19-Pad1)") (class "Default")
      (node (ref "MN19") (pin "1") (pinfunction "1_1") (pintype "passive"))
      (node (ref "MN24") (pin "2") (pinfunction "2_2") (pintype "passive"))
    )
    (net (code "69") (name "Net-(MN20-Pad1)") (class "Default")
      (node (ref "MN20") (pin "1") (pinfunction "1_1") (pintype "passive"))
      (node (ref "MN25") (pin "2") (pinfunction "2_2") (pintype "passive"))
    )
    (net (code "70") (name "VCC1P8_LMS") (class "Default")
      (node (ref "C10") (pin "2") (pinfunction "2_2") (pintype "passive"))
      (node (ref "C11") (pin "2") (pinfunction "2_2") (pintype "passive"))
      (node (ref "C12") (pin "2") (pinfunction "2_2") (pintype "passive"))
      (node (ref "C13") (pin "2") (pinfunction "2_2") (pintype "passive"))
      (node (ref "C4") (pin "2") (pinfunction "2_2") (pintype "passive"))
      (node (ref "C5") (pin "2") (pinfunction "2_2") (pintype "passive"))
      (node (ref "C6") (pin "2") (pinfunction "2_2") (pintype "passive"))
      (node (ref "C7") (pin "2") (pinfunction "2_2") (pintype "passive"))
      (node (ref "MN1") (pin "2") (pinfunction "2_2") (pintype "passive"))
      (node (ref "MN17") (pin "2") (pinfunction "2_2") (pintype "passive"))
      (node (ref "MN18") (pin "2") (pinfunction "2_2") (pintype "passive"))
      (node (ref "MN19") (pin "2") (pinfunction "2_2") (pintype "passive"))
      (node (ref "MN2") (pin "2") (pinfunction "2_2") (pintype "passive"))
      (node (ref "MN20") (pin "2") (pinfunction "2_2") (pintype "passive"))
      (node (ref "MN3") (pin "2") (pinfunction "2_2") (pintype "passive"))
      (node (ref "MN4") (pin "2") (pinfunction "2_2") (pintype "passive"))
    )
  )
)
